# JacdacEc30Template30x20_104.net
KiCad netlist of a schematic drawn in Altium Designer
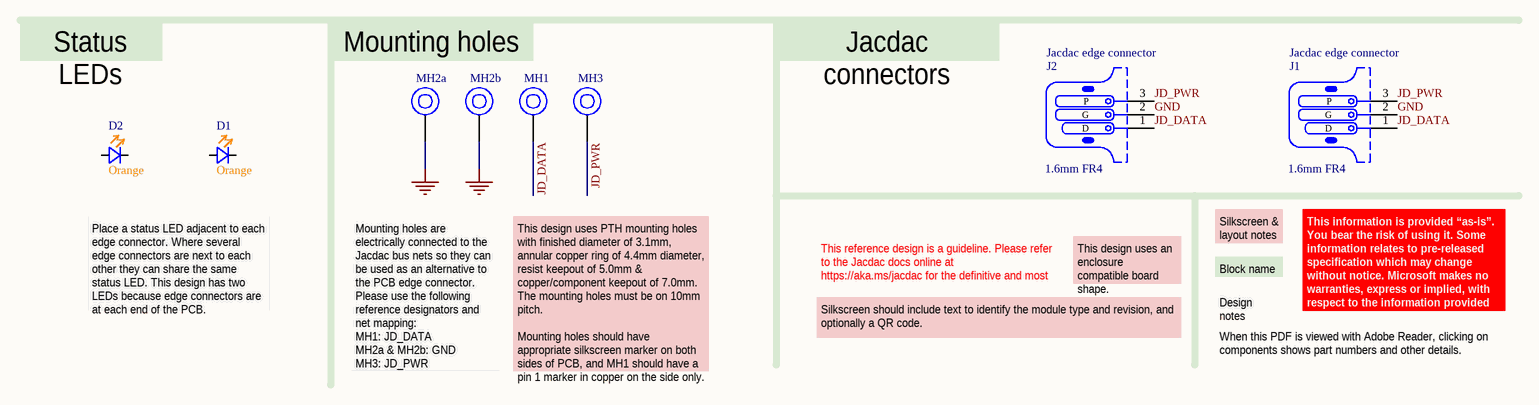
[diagram p0: JacdacEc30Template30x20 104.SchDoc]

(export (version "E")
  (design (tool "Eeschema 10.0.6"))
  (components
    (comp (ref "D1")
      (value "~")
      (footprint "0603 Orange")
      (description "LED ORANGE DIFFUSED 0603 SMD")
      (fields
        (field (name "MANUFACTURER") "Everlight Elec")
        (field (name "MANUFACTURER PART NUMBER") "19-217/S2C-AQ1R1B/3T")
        (field (name "COLOUR") "Orange")
      )
      (libsource (lib "EverlightElec") (part "19-217/S2C-AQ1R1B/3T"))
    )
    (comp (ref "D2")
      (value "~")
      (footprint "0603 Orange")
      (description "LED ORANGE DIFFUSED 0603 SMD")
      (fields
        (field (name "MANUFACTURER") "Everlight Elec")
        (field (name "MANUFACTURER PART NUMBER") "19-217/S2C-AQ1R1B/3T")
        (field (name "COLOUR") "Orange")
      )
      (libsource (lib "EverlightElec") (part "19-217/S2C-AQ1R1B/3T"))
    )
    (comp (ref "J1")
      (value "Jacdac edge connector")
      (footprint "JACDAC_edge_connector:JACDAC_EDGE_CONNECTOR_NO_TRACES_V2DIMS")
      (description "3 pin Jacdac edge connector 1.27mm pitch")
      (fields
        (field (name "MANUFACTURER PART NUMBER") "JACDAC_EDGE_CONNECTOR")
        (field (name "PCB TYPE") "1.6mm FR4")
        (field (name "CHECKED BY") "?")
        (field (name "CREATED BY") "D. Gakure")
      )
      (libsource (lib "generic-con") (part "Jacdac edge connector"))
    )
    (comp (ref "J2")
      (value "Jacdac edge connector")
      (footprint "JACDAC_edge_connector:JACDAC_EDGE_CONNECTOR_NO_TRACES_V2DIMS")
      (description "3 pin Jacdac edge connector 1.27mm pitch")
      (fields
        (field (name "MANUFACTURER PART NUMBER") "JACDAC_EDGE_CONNECTOR")
        (field (name "PCB TYPE") "1.6mm FR4")
        (field (name "CHECKED BY") "?")
        (field (name "CREATED BY") "D. Gakure")
      )
      (libsource (lib "generic-con") (part "Jacdac edge connector"))
    )
    (comp (ref "MH1")
      (value "MH_6.5MMK_4.5MMC_3.0MMD_PTH")
      (footprint "MH_6.5MMK_4.5MMC_3.0MMD_PTH")
      (description "Mounting Hole 6.5mm keepout, 4.5mm annualar ring and 3.0mm Drill PTH")
      (libsource (lib "generic") (part "MH_6.5MMK_4.5MMC_3.0MMD_PTH"))
    )
    (comp (ref "MH2a")
      (value "MH_6.5MMK_4.5MMC_3.0MMD_PTH")
      (footprint "MH_6.5MMK_4.5MMC_3.0MMD_PTH")
      (description "Mounting Hole 6.5mm keepout, 4.5mm annualar ring and 3.0mm Drill PTH")
      (libsource (lib "generic") (part "MH_6.5MMK_4.5MMC_3.0MMD_PTH"))
    )
    (comp (ref "MH2b")
      (value "MH_6.5MMK_4.5MMC_3.0MMD_PTH")
      (footprint "MH_6.5MMK_4.5MMC_3.0MMD_PTH")
      (description "Mounting Hole 6.5mm keepout, 4.5mm annualar ring and 3.0mm Drill PTH")
      (libsource (lib "generic") (part "MH_6.5MMK_4.5MMC_3.0MMD_PTH"))
    )
    (comp (ref "MH3")
      (value "MH_6.5MMK_4.5MMC_3.0MMD_PTH")
      (footprint "MH_6.5MMK_4.5MMC_3.0MMD_PTH")
      (description "Mounting Hole 6.5mm keepout, 4.5mm annualar ring and 3.0mm Drill PTH")
      (libsource (lib "generic") (part "MH_6.5MMK_4.5MMC_3.0MMD_PTH"))
    )
  )
  (nets
    (net (code "1") (name "/JD_DATA") (class "Default")
      (node (ref "J1") (pin "1") (pinfunction "D_1") (pintype "passive"))
      (node (ref "J2") (pin "1") (pinfunction "D_1") (pintype "passive"))
      (node (ref "MH1") (pin "1") (pinfunction "1_1") (pintype "passive"))
    )
    (net (code "2") (name "/JD_PWR") (class "Default")
      (node (ref "J1") (pin "3") (pinfunction "P_3") (pintype "passive"))
      (node (ref "J2") (pin "3") (pinfunction "P_3") (pintype "passive"))
      (node (ref "MH3") (pin "1") (pinfunction "1_1") (pintype "passive"))
    )
    (net (code "3") (name "GND") (class "Default")
      (node (ref "J1") (pin "2") (pinfunction "G_2") (pintype "passive"))
      (node (ref "J2") (pin "2") (pinfunction "G_2") (pintype "passive"))
      (node (ref "MH2a") (pin "1") (pinfunction "1_1") (pintype "passive"))
      (node (ref "MH2b") (pin "1") (pinfunction "1_1") (pintype "passive"))
    )
    (net (code "4") (name "unconnected-(D1-A-Pad2)") (class "Default")
      (node (ref "D1") (pin "2") (pinfunction "A_2") (pintype "passive"))
    )
    (net (code "5") (name "unconnected-(D1-K-Pad1)") (class "Default")
      (node (ref "D1") (pin "1") (pinfunction "K_1") (pintype "passive"))
    )
    (net (code "6") (name "unconnected-(D2-A-Pad2)") (class "Default")
      (node (ref "D2") (pin "2") (pinfunction "A_2") (pintype "passive"))
    )
    (net (code "7") (name "unconnected-(D2-K-Pad1)") (class "Default")
      (node (ref "D2") (pin "1") (pinfunction "K_1") (pintype "passive"))
    )
  )
)
